# pmic_tps65263_buck.net
KiCad netlist of a schematic drawn in Altium Designer
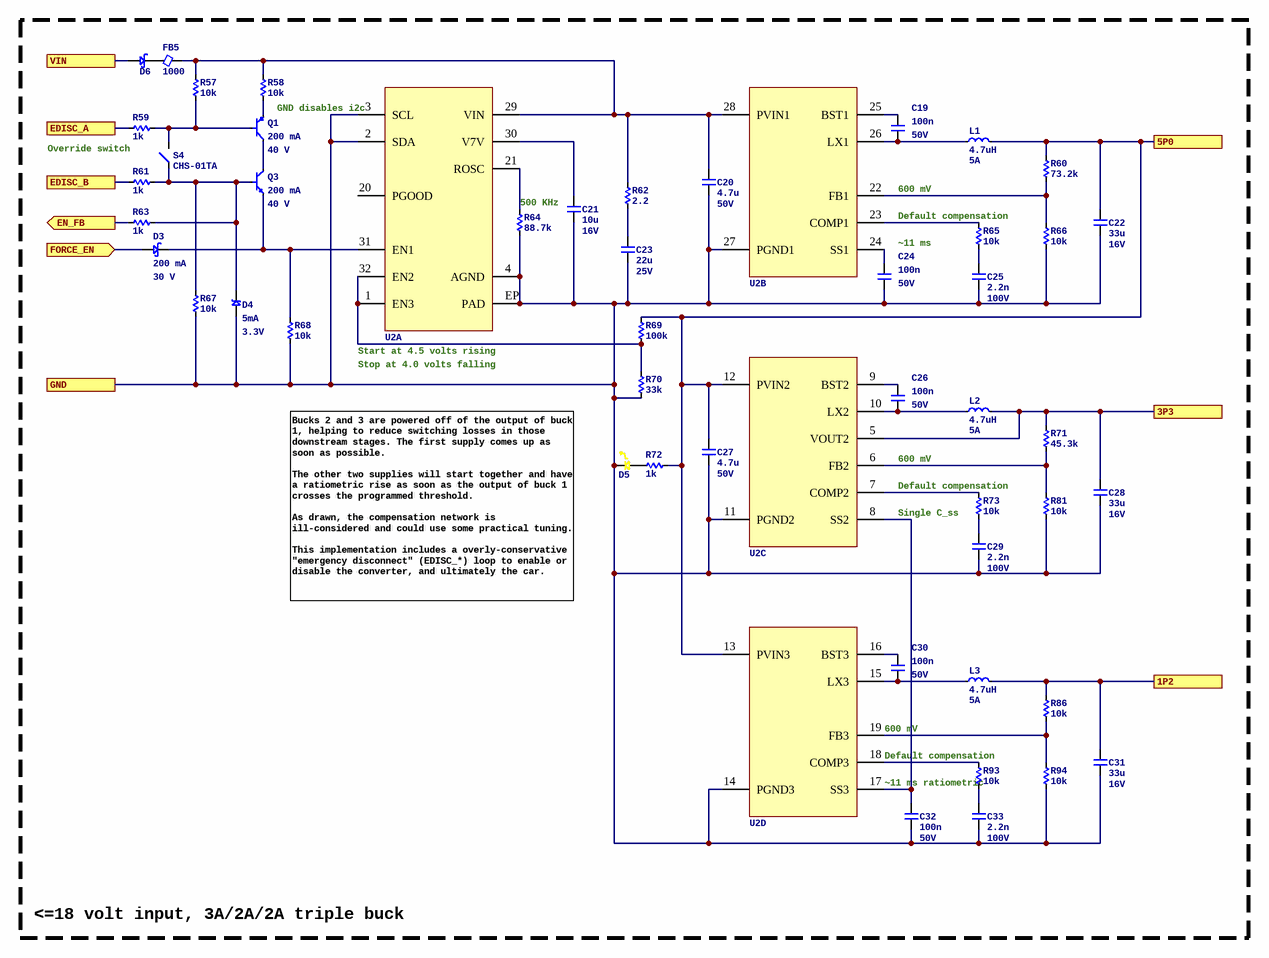
[diagram p0: pmic_tps65263_buck.SchDoc]

(export (version "E")
  (design (tool "Eeschema 10.0.6"))
  (components
    (comp (ref "C19")
      (value "CL05B104KB54PNC")
      (footprint "C0402")
      (fields
        (field (name "CAPACITANCE") "100n")
        (field (name "MANUFACTURER") "Samsung Electro-Mechanics")
        (field (name "VOLTAGE RATING") "50V")
      )
      (libsource (lib "database") (part "__template_cap"))
    )
    (comp (ref "C20")
      (value "0805B475K500NT")
      (footprint "C0805")
      (fields
        (field (name "CAPACITANCE") "4.7u")
        (field (name "MANUFACTURER") "FH (Guangdong Fenghua Advanced Tech)")
        (field (name "VOLTAGE RATING") "50V")
      )
      (libsource (lib "database") (part "__template_cap"))
    )
    (comp (ref "C21")
      (value "CL21B106KOQNNNE")
      (footprint "C0805")
      (fields
        (field (name "CAPACITANCE") "10u")
        (field (name "MANUFACTURER") "Samsung Electro-Mechanics")
        (field (name "VOLTAGE RATING") "16V")
      )
      (libsource (lib "database") (part "__template_cap"))
    )
    (comp (ref "C22")
      (value "C4532X7R1C336MT000N")
      (footprint "C1812")
      (fields
        (field (name "CAPACITANCE") "33u")
        (field (name "MANUFACTURER") "TDK")
        (field (name "VOLTAGE RATING") "16V")
      )
      (libsource (lib "database") (part "__template_cap"))
    )
    (comp (ref "C23")
      (value "C5750X7R1E226MT000N")
      (footprint "C2220")
      (fields
        (field (name "CAPACITANCE") "22u")
        (field (name "MANUFACTURER") "TDK")
        (field (name "VOLTAGE RATING") "25V")
      )
      (libsource (lib "database") (part "__template_cap"))
    )
    (comp (ref "C24")
      (value "CL05B104KB54PNC")
      (footprint "C0402")
      (fields
        (field (name "CAPACITANCE") "100n")
        (field (name "MANUFACTURER") "Samsung Electro-Mechanics")
        (field (name "VOLTAGE RATING") "50V")
      )
      (libsource (lib "database") (part "__template_cap"))
    )
    (comp (ref "C25")
      (value "CC0402KRX7R0BB222")
      (footprint "C0402")
      (fields
        (field (name "CAPACITANCE") "2.2n")
        (field (name "MANUFACTURER") "YAGEO")
        (field (name "VOLTAGE RATING") "100V")
      )
      (libsource (lib "database") (part "__template_cap"))
    )
    (comp (ref "C26")
      (value "CL05B104KB54PNC")
      (footprint "C0402")
      (fields
        (field (name "CAPACITANCE") "100n")
        (field (name "MANUFACTURER") "Samsung Electro-Mechanics")
        (field (name "VOLTAGE RATING") "50V")
      )
      (libsource (lib "database") (part "__template_cap"))
    )
    (comp (ref "C27")
      (value "0805B475K500NT")
      (footprint "C0805")
      (fields
        (field (name "CAPACITANCE") "4.7u")
        (field (name "MANUFACTURER") "FH (Guangdong Fenghua Advanced Tech)")
        (field (name "VOLTAGE RATING") "50V")
      )
      (libsource (lib "database") (part "__template_cap"))
    )
    (comp (ref "C28")
      (value "C4532X7R1C336MT000N")
      (footprint "C1812")
      (fields
        (field (name "CAPACITANCE") "33u")
        (field (name "MANUFACTURER") "TDK")
        (field (name "VOLTAGE RATING") "16V")
      )
      (libsource (lib "database") (part "__template_cap"))
    )
    (comp (ref "C29")
      (value "CC0402KRX7R0BB222")
      (footprint "C0402")
      (fields
        (field (name "CAPACITANCE") "2.2n")
        (field (name "MANUFACTURER") "YAGEO")
        (field (name "VOLTAGE RATING") "100V")
      )
      (libsource (lib "database") (part "__template_cap"))
    )
    (comp (ref "C30")
      (value "CL05B104KB54PNC")
      (footprint "C0402")
      (fields
        (field (name "CAPACITANCE") "100n")
        (field (name "MANUFACTURER") "Samsung Electro-Mechanics")
        (field (name "VOLTAGE RATING") "50V")
      )
      (libsource (lib "database") (part "__template_cap"))
    )
    (comp (ref "C31")
      (value "C4532X7R1C336MT000N")
      (footprint "C1812")
      (fields
        (field (name "CAPACITANCE") "33u")
        (field (name "MANUFACTURER") "TDK")
        (field (name "VOLTAGE RATING") "16V")
      )
      (libsource (lib "database") (part "__template_cap"))
    )
    (comp (ref "C32")
      (value "CL05B104KB54PNC")
      (footprint "C0402")
      (fields
        (field (name "CAPACITANCE") "100n")
        (field (name "MANUFACTURER") "Samsung Electro-Mechanics")
        (field (name "VOLTAGE RATING") "50V")
      )
      (libsource (lib "database") (part "__template_cap"))
    )
    (comp (ref "C33")
      (value "CC0402KRX7R0BB222")
      (footprint "C0402")
      (fields
        (field (name "CAPACITANCE") "2.2n")
        (field (name "MANUFACTURER") "YAGEO")
        (field (name "VOLTAGE RATING") "100V")
      )
      (libsource (lib "database") (part "__template_cap"))
    )
    (comp (ref "D3")
      (value "BAT54XV2T1G")
      (footprint "SOD523")
      (description "ON Semi BAT54XV2T1G; SMT Schottky Diode; 30V 200mA; 5ns; 2-Pin SOD-523")
      (fields
        (field (name "MANUFACTURER") "onsemi")
        (field (name "CURRENT") "200 mA")
        (field (name "VOLTAGE") "30 V")
      )
      (libsource (lib "SSCP") (part "SCHOTTKY_30V_BAT54XV2T1G"))
    )
    (comp (ref "D4")
      (value "SZMM5Z3V3T1G")
      (footprint "SOD523")
      (description "500 mW Standard Tolerance Zener Diode Voltage Regulators 3.3 V (Automotive)")
      (fields
        (field (name "MANUFACTURER") "onsemi")
        (field (name "CURRENT") "5mA")
        (field (name "VOLTAGE") "3.3V")
      )
      (libsource (lib "SSCP") (part "ZENER_3.3V_SZMM5Z3V3T1G"))
    )
    (comp (ref "D5")
      (value "LTST-C190YKT")
      (footprint "LED_0603P_YELLOW")
      (description "LED YELLOW CLEAR 0603 SMD")
      (fields (field (name "MANUFACTURER") "Lite-On Inc"))
      (libsource (lib "SSCP") (part "LED_0603_YELLOW_LTST-C190YKT"))
    )
    (comp (ref "D6")
      (value "B340A-13-F")
      (footprint "SMA")
      (description "Rectifier Diode, Schottky, 1 Phase, 1 Element, 3A, 40V V(RRM), Silicon")
      (fields (field (name "MANUFACTURER") "Diodes"))
      (libsource (lib "SSCP") (part "SCHOTTKY_B340A-13-F"))
    )
    (comp (ref "FB5")
      (value "HCB2012KF-102T10")
      (footprint "FB0805")
      (fields (field (name "MANUFACTURER") "TAI-TECH") (field (name "CURRENT RATING (MA)") "1000"))
      (libsource (lib "database") (part "__template_fb"))
    )
    (comp (ref "L1")
      (value "4.7uH")
      (footprint "SMD-4.1x4.1x2.0")
      (description "5A 4.7uH 6.3A 58mΩ ±20% SMD,4.1x4.1mm Fixed Inductors RoHS")
      (fields
        (field (name "MANUFACTURER PART NUMBER") "FTC404020S4R7MGCA")
        (field (name "MANUFACTURER") "cjiang")
        (field (name "CURRENT") "5A")
      )
      (libsource (lib "SSCP") (part "IND_4.7UH_FTC404020S4R7MGCA"))
    )
    (comp (ref "L2")
      (value "4.7uH")
      (footprint "SMD-4.1x4.1x2.0")
      (description "5A 4.7uH 6.3A 58mΩ ±20% SMD,4.1x4.1mm Fixed Inductors RoHS")
      (fields
        (field (name "MANUFACTURER PART NUMBER") "FTC404020S4R7MGCA")
        (field (name "MANUFACTURER") "cjiang")
        (field (name "CURRENT") "5A")
      )
      (libsource (lib "SSCP") (part "IND_4.7UH_FTC404020S4R7MGCA"))
    )
    (comp (ref "L3")
      (value "4.7uH")
      (footprint "SMD-4.1x4.1x2.0")
      (description "5A 4.7uH 6.3A 58mΩ ±20% SMD,4.1x4.1mm Fixed Inductors RoHS")
      (fields
        (field (name "MANUFACTURER PART NUMBER") "FTC404020S4R7MGCA")
        (field (name "MANUFACTURER") "cjiang")
        (field (name "CURRENT") "5A")
      )
      (libsource (lib "SSCP") (part "IND_4.7UH_FTC404020S4R7MGCA"))
    )
    (comp (ref "Q1")
      (value "MMBT3906T")
      (footprint "3SOT523")
      (description "Bipolar (BJT) Transistor NPN 40 V 200 mA 300MHz 150 mW Surface Mount SOT-523")
      (fields
        (field (name "MANUFACTURER") "Shenzhen Slkormicro Semicon Co., Ltd.")
        (field (name "CURRENT") "200 mA")
        (field (name "VOLTAGE") "40 V")
      )
      (libsource (lib "SSCP") (part "PNP_40V_MMBT3906T"))
    )
    (comp (ref "Q3")
      (value "MMBT3904T")
      (footprint "3SOT523")
      (description "Bipolar (BJT) Transistor NPN 40 V 200 mA 300MHz 150 mW Surface Mount SOT-523")
      (fields
        (field (name "MANUFACTURER") "Shenzhen Slkormicro Semicon Co., Ltd.")
        (field (name "CURRENT") "200 mA")
        (field (name "VOLTAGE") "40 V")
      )
      (libsource (lib "SSCP") (part "NPN_40V_MMBT3904T"))
    )
    (comp (ref "R57")
      (value "10k")
      (footprint "R0402")
      (fields
        (field (name "TOLERANCE") "1%")
        (field (name "MANUFACTURER PART NUMBER") "0402WGF1002TCE")
        (field (name "MANUFACTURER") "UNI-ROYAL(Uniroyal Elec)")
      )
      (libsource (lib "database") (part "__template_resistor"))
    )
    (comp (ref "R58")
      (value "10k")
      (footprint "R0402")
      (fields
        (field (name "TOLERANCE") "1%")
        (field (name "MANUFACTURER PART NUMBER") "0402WGF1002TCE")
        (field (name "MANUFACTURER") "UNI-ROYAL(Uniroyal Elec)")
      )
      (libsource (lib "database") (part "__template_resistor"))
    )
    (comp (ref "R59")
      (value "1k")
      (footprint "R0402")
      (fields
        (field (name "TOLERANCE") "1%")
        (field (name "MANUFACTURER PART NUMBER") "0402WGF1001TCE")
        (field (name "MANUFACTURER") "UNI-ROYAL(Uniroyal Elec)")
      )
      (libsource (lib "database") (part "__template_resistor"))
    )
    (comp (ref "R60")
      (value "73.2k")
      (footprint "R0402")
      (fields
        (field (name "TOLERANCE") "1%")
        (field (name "MANUFACTURER PART NUMBER") "0402WGF7322TCE")
        (field (name "MANUFACTURER") "UNI-ROYAL(Uniroyal Elec)")
      )
      (libsource (lib "database") (part "__template_resistor"))
    )
    (comp (ref "R61")
      (value "1k")
      (footprint "R0402")
      (fields
        (field (name "TOLERANCE") "1%")
        (field (name "MANUFACTURER PART NUMBER") "0402WGF1001TCE")
        (field (name "MANUFACTURER") "UNI-ROYAL(Uniroyal Elec)")
      )
      (libsource (lib "database") (part "__template_resistor"))
    )
    (comp (ref "R62")
      (value "2.2")
      (footprint "R0805")
      (fields
        (field (name "TOLERANCE") "1%")
        (field (name "MANUFACTURER PART NUMBER") "HP05W3F220KT5E")
        (field (name "MANUFACTURER") "UNI-ROYAL(Uniroyal Elec)")
      )
      (libsource (lib "database") (part "__template_resistor"))
    )
    (comp (ref "R63")
      (value "1k")
      (footprint "R0402")
      (fields
        (field (name "TOLERANCE") "1%")
        (field (name "MANUFACTURER PART NUMBER") "0402WGF1001TCE")
        (field (name "MANUFACTURER") "UNI-ROYAL(Uniroyal Elec)")
      )
      (libsource (lib "database") (part "__template_resistor"))
    )
    (comp (ref "R64")
      (value "88.7k")
      (footprint "R0402")
      (fields
        (field (name "TOLERANCE") "1%")
        (field (name "MANUFACTURER PART NUMBER") "0402WGF8872TCE")
        (field (name "MANUFACTURER") "UNI-ROYAL(Uniroyal Elec)")
      )
      (libsource (lib "database") (part "__template_resistor"))
    )
    (comp (ref "R65")
      (value "10k")
      (footprint "R0402")
      (fields
        (field (name "TOLERANCE") "1%")
        (field (name "MANUFACTURER PART NUMBER") "0402WGF1002TCE")
        (field (name "MANUFACTURER") "UNI-ROYAL(Uniroyal Elec)")
      )
      (libsource (lib "database") (part "__template_resistor"))
    )
    (comp (ref "R66")
      (value "10k")
      (footprint "R0402")
      (fields
        (field (name "TOLERANCE") "1%")
        (field (name "MANUFACTURER PART NUMBER") "0402WGF1002TCE")
        (field (name "MANUFACTURER") "UNI-ROYAL(Uniroyal Elec)")
      )
      (libsource (lib "database") (part "__template_resistor"))
    )
    (comp (ref "R67")
      (value "10k")
      (footprint "R0402")
      (fields
        (field (name "TOLERANCE") "1%")
        (field (name "MANUFACTURER PART NUMBER") "0402WGF1002TCE")
        (field (name "MANUFACTURER") "UNI-ROYAL(Uniroyal Elec)")
      )
      (libsource (lib "database") (part "__template_resistor"))
    )
    (comp (ref "R68")
      (value "10k")
      (footprint "R0402")
      (fields
        (field (name "TOLERANCE") "1%")
        (field (name "MANUFACTURER PART NUMBER") "0402WGF1002TCE")
        (field (name "MANUFACTURER") "UNI-ROYAL(Uniroyal Elec)")
      )
      (libsource (lib "database") (part "__template_resistor"))
    )
    (comp (ref "R69")
      (value "100k")
      (footprint "R0402")
      (fields
        (field (name "TOLERANCE") "1%")
        (field (name "MANUFACTURER PART NUMBER") "0402WGF1003TCE")
        (field (name "MANUFACTURER") "UNI-ROYAL(Uniroyal Elec)")
      )
      (libsource (lib "database") (part "__template_resistor"))
    )
    (comp (ref "R70")
      (value "33k")
      (footprint "R0402")
      (fields
        (field (name "TOLERANCE") "1%")
        (field (name "MANUFACTURER PART NUMBER") "0402WGF3302TCE")
        (field (name "MANUFACTURER") "UNI-ROYAL(Uniroyal Elec)")
      )
      (libsource (lib "database") (part "__template_resistor"))
    )
    (comp (ref "R71")
      (value "45.3k")
      (footprint "R0402")
      (fields
        (field (name "TOLERANCE") "1%")
        (field (name "MANUFACTURER PART NUMBER") "FRC0402F4532TS")
        (field (name "MANUFACTURER") "FOJAN")
      )
      (libsource (lib "database") (part "__template_resistor"))
    )
    (comp (ref "R72")
      (value "1k")
      (footprint "R0402")
      (fields
        (field (name "TOLERANCE") "1%")
        (field (name "MANUFACTURER PART NUMBER") "0402WGF1001TCE")
        (field (name "MANUFACTURER") "UNI-ROYAL(Uniroyal Elec)")
      )
      (libsource (lib "database") (part "__template_resistor"))
    )
    (comp (ref "R73")
      (value "10k")
      (footprint "R0402")
      (fields
        (field (name "TOLERANCE") "1%")
        (field (name "MANUFACTURER PART NUMBER") "0402WGF1002TCE")
        (field (name "MANUFACTURER") "UNI-ROYAL(Uniroyal Elec)")
      )
      (libsource (lib "database") (part "__template_resistor"))
    )
    (comp (ref "R81")
      (value "10k")
      (footprint "R0402")
      (fields
        (field (name "TOLERANCE") "1%")
        (field (name "MANUFACTURER PART NUMBER") "0402WGF1002TCE")
        (field (name "MANUFACTURER") "UNI-ROYAL(Uniroyal Elec)")
      )
      (libsource (lib "database") (part "__template_resistor"))
    )
    (comp (ref "R86")
      (value "10k")
      (footprint "R0402")
      (fields
        (field (name "TOLERANCE") "1%")
        (field (name "MANUFACTURER PART NUMBER") "0402WGF1002TCE")
        (field (name "MANUFACTURER") "UNI-ROYAL(Uniroyal Elec)")
      )
      (libsource (lib "database") (part "__template_resistor"))
    )
    (comp (ref "R93")
      (value "10k")
      (footprint "R0402")
      (fields
        (field (name "TOLERANCE") "1%")
        (field (name "MANUFACTURER PART NUMBER") "0402WGF1002TCE")
        (field (name "MANUFACTURER") "UNI-ROYAL(Uniroyal Elec)")
      )
      (libsource (lib "database") (part "__template_resistor"))
    )
    (comp (ref "R94")
      (value "10k")
      (footprint "R0402")
      (fields
        (field (name "TOLERANCE") "1%")
        (field (name "MANUFACTURER PART NUMBER") "0402WGF1002TCE")
        (field (name "MANUFACTURER") "UNI-ROYAL(Uniroyal Elec)")
      )
      (libsource (lib "database") (part "__template_resistor"))
    )
    (comp (ref "S4")
      (value "CHS-01TA")
      (footprint "SWITCH_NIDEC_CHS-01TA")
      (description "DIP Switch, Slide, SPST, Flush, Recessed, 6VDC, 100mA, CHS Series ¦ Nidec Components CHS-01TA")
      (fields (field (name "MANUFACTURER") "Nidec Copal"))
      (libsource (lib "SSCP") (part "SWITCH_CHS-01TA"))
    )
    (comp (ref "U2")
      (value "TPS65263QRHBRQ1")
      (footprint "TI_RHB")
      (description "Switching Regulator, Current-mode, 3A, 2300kHz Switching Freq-Max, PQCC32")
      (fields (field (name "MANUFACTURER") "Texas Instruments"))
      (libsource (lib "SSCP") (part "BUCK_TPS65263QRHBRQ1"))
    )
  )
  (nets
    (net (code "1") (name "/1P2") (class "Default")
      (node (ref "C31") (pin "1") (pintype "passive"))
      (node (ref "L3") (pin "2") (pintype "passive"))
      (node (ref "R86") (pin "2") (pintype "passive"))
    )
    (net (code "2") (name "/3P3") (class "Default")
      (node (ref "C28") (pin "1") (pintype "passive"))
      (node (ref "L2") (pin "2") (pintype "passive"))
      (node (ref "R71") (pin "2") (pintype "passive"))
      (node (ref "U2") (pin "5") (pinfunction "VOUT2_5") (pintype "passive"))
    )
    (net (code "3") (name "/5P0") (class "Default")
      (node (ref "C22") (pin "1") (pintype "passive"))
      (node (ref "C27") (pin "1") (pintype "passive"))
      (node (ref "L1") (pin "2") (pintype "passive"))
      (node (ref "R60") (pin "2") (pintype "passive"))
      (node (ref "R69") (pin "2") (pintype "passive"))
      (node (ref "R72") (pin "2") (pintype "passive"))
      (node (ref "U2") (pin "12") (pinfunction "PVIN2_12") (pintype "passive"))
      (node (ref "U2") (pin "13") (pinfunction "PVIN3_13") (pintype "passive"))
    )
    (net (code "4") (name "/EDISC_A") (class "Default") (node (ref "R59") (pin "1") (pintype "passive")))
    (net (code "5") (name "/EDISC_B") (class "Default") (node (ref "R61") (pin "1") (pintype "passive")))
    (net (code "6") (name "/EN_FB") (class "Default") (node (ref "R63") (pin "1") (pintype "passive")))
    (net (code "7") (name "/FORCE_EN") (class "Default") (node (ref "D3") (pin "1") (pintype "passive")))
    (net (code "8") (name "/GND") (class "Default")
      (node (ref "C20") (pin "2") (pintype "passive"))
      (node (ref "C21") (pin "2") (pintype "passive"))
      (node (ref "C22") (pin "2") (pintype "passive"))
      (node (ref "C23") (pin "2") (pintype "passive"))
      (node (ref "C24") (pin "2") (pintype "passive"))
      (node (ref "C25") (pin "2") (pintype "passive"))
      (node (ref "C27") (pin "2") (pintype "passive"))
      (node (ref "C28") (pin "2") (pintype "passive"))
      (node (ref "C29") (pin "2") (pintype "passive"))
      (node (ref "C31") (pin "2") (pintype "passive"))
      (node (ref "C32") (pin "2") (pintype "passive"))
      (node (ref "C33") (pin "2") (pintype "passive"))
      (node (ref "D4") (pin "1") (pintype "passive"))
      (node (ref "D5") (pin "1") (pintype "passive"))
      (node (ref "R64") (pin "1") (pintype "passive"))
      (node (ref "R66") (pin "1") (pintype "passive"))
      (node (ref "R67") (pin "1") (pintype "passive"))
      (node (ref "R68") (pin "1") (pintype "passive"))
      (node (ref "R70") (pin "1") (pintype "passive"))
      (node (ref "R81") (pin "1") (pintype "passive"))
      (node (ref "R94") (pin "1") (pintype "passive"))
      (node (ref "U2") (pin "11") (pinfunction "PGND2_11") (pintype "passive"))
      (node (ref "U2") (pin "14") (pinfunction "PGND3_14") (pintype "passive"))
      (node (ref "U2") (pin "2") (pinfunction "SDA_2") (pintype "passive"))
      (node (ref "U2") (pin "27") (pinfunction "PGND1_27") (pintype "passive"))
      (node (ref "U2") (pin "3") (pinfunction "SCL_3") (pintype "passive"))
      (node (ref "U2") (pin "4") (pinfunction "AGND_4") (pintype "passive"))
      (node (ref "U2") (pin "EP") (pinfunction "PAD_EP") (pintype "passive"))
    )
    (net (code "9") (name "/VIN") (class "Default") (node (ref "D6") (pin "1") (pintype "passive")))
    (net (code "10") (name "Net-(C23-Pad1)") (class "Default")
      (node (ref "C23") (pin "1") (pintype "passive"))
      (node (ref "R62") (pin "1") (pintype "passive"))
    )
    (net (code "11") (name "Net-(C25-Pad1)") (class "Default")
      (node (ref "C25") (pin "1") (pintype "passive"))
      (node (ref "R65") (pin "1") (pintype "passive"))
    )
    (net (code "12") (name "Net-(C29-Pad1)") (class "Default")
      (node (ref "C29") (pin "1") (pintype "passive"))
      (node (ref "R73") (pin "1") (pintype "passive"))
    )
    (net (code "13") (name "Net-(C33-Pad1)") (class "Default")
      (node (ref "C33") (pin "1") (pintype "passive"))
      (node (ref "R93") (pin "1") (pintype "passive"))
    )
    (net (code "14") (name "Net-(D5-Pad2)") (class "Default")
      (node (ref "D5") (pin "2") (pintype "passive"))
      (node (ref "R72") (pin "1") (pintype "passive"))
    )
    (net (code "15") (name "Net-(D6-Pad2)") (class "Default")
      (node (ref "D6") (pin "2") (pintype "passive"))
      (node (ref "FB5") (pin "1") (pintype "passive"))
    )
    (net (code "16") (name "Net-(Q1-B)") (class "Default")
      (node (ref "Q1") (pin "1") (pinfunction "B_1") (pintype "passive"))
      (node (ref "R57") (pin "1") (pintype "passive"))
      (node (ref "R59") (pin "2") (pintype "passive"))
      (node (ref "S4") (pin "2") (pintype "passive"))
    )
    (net (code "17") (name "Net-(Q1-C)") (class "Default")
      (node (ref "Q1") (pin "3") (pinfunction "C_3") (pintype "passive"))
      (node (ref "Q3") (pin "3") (pinfunction "C_3") (pintype "passive"))
    )
    (net (code "18") (name "Net-(Q1-E)") (class "Default")
      (node (ref "Q1") (pin "2") (pinfunction "E_2") (pintype "passive"))
      (node (ref "R58") (pin "1") (pintype "passive"))
    )
    (net (code "19") (name "Net-(Q3-B)") (class "Default")
      (node (ref "D4") (pin "2") (pintype "passive"))
      (node (ref "Q3") (pin "1") (pinfunction "B_1") (pintype "passive"))
      (node (ref "R61") (pin "2") (pintype "passive"))
      (node (ref "R63") (pin "2") (pintype "passive"))
      (node (ref "R67") (pin "2") (pintype "passive"))
      (node (ref "S4") (pin "1") (pintype "passive"))
    )
    (net (code "20") (name "Net-(Q3-E)") (class "Default")
      (node (ref "D3") (pin "2") (pintype "passive"))
      (node (ref "Q3") (pin "2") (pinfunction "E_2") (pintype "passive"))
      (node (ref "R68") (pin "2") (pintype "passive"))
      (node (ref "U2") (pin "31") (pinfunction "EN1_31") (pintype "passive"))
    )
    (net (code "21") (name "Net-(U2A-EN2)") (class "Default")
      (node (ref "R69") (pin "1") (pintype "passive"))
      (node (ref "R70") (pin "2") (pintype "passive"))
      (node (ref "U2") (pin "1") (pinfunction "EN3_1") (pintype "passive"))
      (node (ref "U2") (pin "32") (pinfunction "EN2_32") (pintype "passive"))
    )
    (net (code "22") (name "Net-(U2A-ROSC)") (class "Default")
      (node (ref "R64") (pin "2") (pintype "passive"))
      (node (ref "U2") (pin "21") (pinfunction "ROSC_21") (pintype "passive"))
    )
    (net (code "23") (name "Net-(U2A-V7V)") (class "Default")
      (node (ref "C21") (pin "1") (pintype "passive"))
      (node (ref "U2") (pin "30") (pinfunction "V7V_30") (pintype "passive"))
    )
    (net (code "24") (name "Net-(U2A-VIN)") (class "Default")
      (node (ref "C20") (pin "1") (pintype "passive"))
      (node (ref "FB5") (pin "2") (pintype "passive"))
      (node (ref "R57") (pin "2") (pintype "passive"))
      (node (ref "R58") (pin "2") (pintype "passive"))
      (node (ref "R62") (pin "2") (pintype "passive"))
      (node (ref "U2") (pin "28") (pinfunction "PVIN1_28") (pintype "passive"))
      (node (ref "U2") (pin "29") (pinfunction "VIN_29") (pintype "passive"))
    )
    (net (code "25") (name "Net-(U2B-BST1)") (class "Default")
      (node (ref "C19") (pin "1") (pintype "passive"))
      (node (ref "U2") (pin "25") (pinfunction "BST1_25") (pintype "passive"))
    )
    (net (code "26") (name "Net-(U2B-COMP1)") (class "Default")
      (node (ref "R65") (pin "2") (pintype "passive"))
      (node (ref "U2") (pin "23") (pinfunction "COMP1_23") (pintype "passive"))
    )
    (net (code "27") (name "Net-(U2B-FB1)") (class "Default")
      (node (ref "R60") (pin "1") (pintype "passive"))
      (node (ref "R66") (pin "2") (pintype "passive"))
      (node (ref "U2") (pin "22") (pinfunction "FB1_22") (pintype "passive"))
    )
    (net (code "28") (name "Net-(U2B-LX1)") (class "Default")
      (node (ref "C19") (pin "2") (pintype "passive"))
      (node (ref "L1") (pin "1") (pintype "passive"))
      (node (ref "U2") (pin "26") (pinfunction "LX1_26") (pintype "passive"))
    )
    (net (code "29") (name "Net-(U2B-SS1)") (class "Default")
      (node (ref "C24") (pin "1") (pintype "passive"))
      (node (ref "U2") (pin "24") (pinfunction "SS1_24") (pintype "passive"))
    )
    (net (code "30") (name "Net-(U2C-BST2)") (class "Default")
      (node (ref "C26") (pin "1") (pintype "passive"))
      (node (ref "U2") (pin "9") (pinfunction "BST2_9") (pintype "passive"))
    )
    (net (code "31") (name "Net-(U2C-COMP2)") (class "Default")
      (node (ref "R73") (pin "2") (pintype "passive"))
      (node (ref "U2") (pin "7") (pinfunction "COMP2_7") (pintype "passive"))
    )
    (net (code "32") (name "Net-(U2C-FB2)") (class "Default")
      (node (ref "R71") (pin "1") (pintype "passive"))
      (node (ref "R81") (pin "2") (pintype "passive"))
      (node (ref "U2") (pin "6") (pinfunction "FB2_6") (pintype "passive"))
    )
    (net (code "33") (name "Net-(U2C-LX2)") (class "Default")
      (node (ref "C26") (pin "2") (pintype "passive"))
      (node (ref "L2") (pin "1") (pintype "passive"))
      (node (ref "U2") (pin "10") (pinfunction "LX2_10") (pintype "passive"))
    )
    (net (code "34") (name "Net-(U2C-SS2)") (class "Default")
      (node (ref "C32") (pin "1") (pintype "passive"))
      (node (ref "U2") (pin "17") (pinfunction "SS3_17") (pintype "passive"))
      (node (ref "U2") (pin "8") (pinfunction "SS2_8") (pintype "passive"))
    )
    (net (code "35") (name "Net-(U2D-BST3)") (class "Default")
      (node (ref "C30") (pin "1") (pintype "passive"))
      (node (ref "U2") (pin "16") (pinfunction "BST3_16") (pintype "passive"))
    )
    (net (code "36") (name "Net-(U2D-COMP3)") (class "Default")
      (node (ref "R93") (pin "2") (pintype "passive"))
      (node (ref "U2") (pin "18") (pinfunction "COMP3_18") (pintype "passive"))
    )
    (net (code "37") (name "Net-(U2D-FB3)") (class "Default")
      (node (ref "R86") (pin "1") (pintype "passive"))
      (node (ref "R94") (pin "2") (pintype "passive"))
      (node (ref "U2") (pin "19") (pinfunction "FB3_19") (pintype "passive"))
    )
    (net (code "38") (name "Net-(U2D-LX3)") (class "Default")
      (node (ref "C30") (pin "2") (pintype "passive"))
      (node (ref "L3") (pin "1") (pintype "passive"))
      (node (ref "U2") (pin "15") (pinfunction "LX3_15") (pintype "passive"))
    )
    (net (code "39") (name "unconnected-(U2A-PGOOD-Pad20)") (class "Default")
      (node (ref "U2") (pin "20") (pinfunction "PGOOD_20") (pintype "passive"))
    )
  )
)
